# bbf-pots.net
KiCad netlist of a schematic drawn in EAGLE
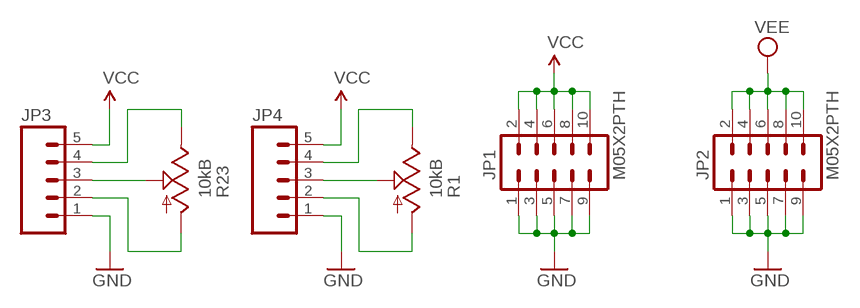
[diagram p0: schematic, sheet 1]

(export (version "E")
  (design (tool "Eeschema 10.0.6"))
  (components
    (comp (ref "JP1")
      (value "M05X2PTH")
      (footprint "eagle-import:AVR_ICSP")
      (libsource (lib "eagle-import") (part "M05X2PTH"))
    )
    (comp (ref "JP2")
      (value "M05X2PTH")
      (footprint "eagle-import:AVR_ICSP")
      (libsource (lib "eagle-import") (part "M05X2PTH"))
    )
    (comp (ref "JP3")
      (value "M05PTH")
      (footprint "eagle-import:1X05")
      (libsource (lib "eagle-import") (part "M05PTH"))
    )
    (comp (ref "JP4")
      (value "M05PTH")
      (footprint "eagle-import:1X05")
      (libsource (lib "eagle-import") (part "M05PTH"))
    )
    (comp (ref "R1")
      (value "10kB")
      (footprint "eagle-import:ALPS_POT_VERTICAL")
      (libsource (lib "eagle-import") (part "POT_USVERTICAL"))
    )
    (comp (ref "R23")
      (value "10kB")
      (footprint "eagle-import:ALPS_POT_VERTICAL")
      (libsource (lib "eagle-import") (part "POT_USVERTICAL"))
    )
  )
  (nets
    (net (code "1") (name "GND") (class "Default")
      (node (ref "JP1") (pin "1") (pinfunction "1_1") (pintype "passive"))
      (node (ref "JP1") (pin "3") (pinfunction "3_3") (pintype "passive"))
      (node (ref "JP1") (pin "5") (pinfunction "5_5") (pintype "passive"))
      (node (ref "JP1") (pin "7") (pinfunction "7_7") (pintype "passive"))
      (node (ref "JP1") (pin "9") (pinfunction "9_9") (pintype "passive"))
      (node (ref "JP2") (pin "1") (pinfunction "1_1") (pintype "passive"))
      (node (ref "JP2") (pin "3") (pinfunction "3_3") (pintype "passive"))
      (node (ref "JP2") (pin "5") (pinfunction "5_5") (pintype "passive"))
      (node (ref "JP2") (pin "7") (pinfunction "7_7") (pintype "passive"))
      (node (ref "JP2") (pin "9") (pinfunction "9_9") (pintype "passive"))
      (node (ref "JP3") (pin "1") (pinfunction "1_1") (pintype "passive"))
      (node (ref "JP4") (pin "1") (pinfunction "1_1") (pintype "passive"))
    )
    (net (code "2") (name "Net-(R1-A)") (class "Default")
      (node (ref "JP4") (pin "2") (pinfunction "2_2") (pintype "passive"))
      (node (ref "R1") (pin "P$3") (pinfunction "A_P$3") (pintype "passive"))
    )
    (net (code "3") (name "Net-(R1-E)") (class "Default")
      (node (ref "JP4") (pin "4") (pinfunction "4_4") (pintype "passive"))
      (node (ref "R1") (pin "P$1") (pinfunction "E_P$1") (pintype "passive"))
    )
    (net (code "4") (name "Net-(R1-S)") (class "Default")
      (node (ref "JP4") (pin "3") (pinfunction "3_3") (pintype "passive"))
      (node (ref "R1") (pin "P$2") (pinfunction "S_P$2") (pintype "passive"))
    )
    (net (code "5") (name "Net-(R23-A)") (class "Default")
      (node (ref "JP3") (pin "2") (pinfunction "2_2") (pintype "passive"))
      (node (ref "R23") (pin "P$3") (pinfunction "A_P$3") (pintype "passive"))
    )
    (net (code "6") (name "Net-(R23-E)") (class "Default")
      (node (ref "JP3") (pin "4") (pinfunction "4_4") (pintype "passive"))
      (node (ref "R23") (pin "P$1") (pinfunction "E_P$1") (pintype "passive"))
    )
    (net (code "7") (name "Net-(R23-S)") (class "Default")
      (node (ref "JP3") (pin "3") (pinfunction "3_3") (pintype "passive"))
      (node (ref "R23") (pin "P$2") (pinfunction "S_P$2") (pintype "passive"))
    )
    (net (code "8") (name "VCC") (class "Default")
      (node (ref "JP1") (pin "10") (pinfunction "10_10") (pintype "passive"))
      (node (ref "JP1") (pin "2") (pinfunction "2_2") (pintype "passive"))
      (node (ref "JP1") (pin "4") (pinfunction "4_4") (pintype "passive"))
      (node (ref "JP1") (pin "6") (pinfunction "6_6") (pintype "passive"))
      (node (ref "JP1") (pin "8") (pinfunction "8_8") (pintype "passive"))
      (node (ref "JP3") (pin "5") (pinfunction "5_5") (pintype "passive"))
      (node (ref "JP4") (pin "5") (pinfunction "5_5") (pintype "passive"))
    )
    (net (code "9") (name "VEE") (class "Default")
      (node (ref "JP2") (pin "10") (pinfunction "10_10") (pintype "passive"))
      (node (ref "JP2") (pin "2") (pinfunction "2_2") (pintype "passive"))
      (node (ref "JP2") (pin "4") (pinfunction "4_4") (pintype "passive"))
      (node (ref "JP2") (pin "6") (pinfunction "6_6") (pintype "passive"))
      (node (ref "JP2") (pin "8") (pinfunction "8_8") (pintype "passive"))
    )
  )
)
